# Supply.net
KiCad netlist of a schematic drawn in Altium Designer
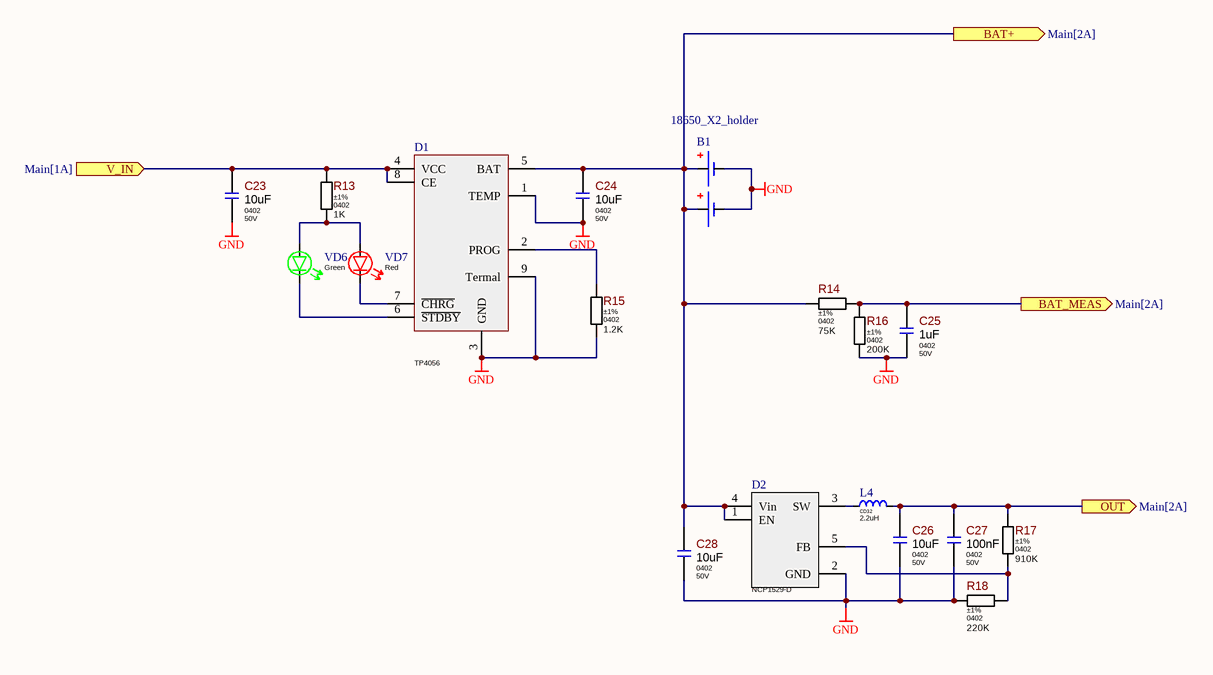
[diagram p0: Supply.SchDoc]

(export (version "E")
  (design (tool "Eeschema 10.0.6"))
  (components
    (comp (ref "B1")
      (value "18650_X2_holder")
      (footprint "18650_X2")
      (libsource (lib "Misc") (part "18650_X2_holder"))
    )
    (comp (ref "C23")
      (value "10uF")
      (footprint "Cap_0402")
      (description "10uF 50V  ±25% 0402 Ceramic Capacitor")
      (fields
        (field (name "TOLERANCE") "±25%")
        (field (name "PACKAGE") "0402")
        (field (name "VOLTAGE") "50V")
      )
      (libsource (lib "Capacitors") (part "Cap_0402_10uF"))
    )
    (comp (ref "C24")
      (value "10uF")
      (footprint "Cap_0402")
      (description "10uF 50V  ±25% 0402 Ceramic Capacitor")
      (fields
        (field (name "TOLERANCE") "±25%")
        (field (name "PACKAGE") "0402")
        (field (name "VOLTAGE") "50V")
      )
      (libsource (lib "Capacitors") (part "Cap_0402_10uF"))
    )
    (comp (ref "C25")
      (value "1uF")
      (footprint "Cap_0402")
      (description "1uF 50V  ±25% 0402 Ceramic Capacitor")
      (fields
        (field (name "TOLERANCE") "±25%")
        (field (name "PACKAGE") "0402")
        (field (name "VOLTAGE") "50V")
      )
      (libsource (lib "Capacitors") (part "Cap_0402_1uF"))
    )
    (comp (ref "C26")
      (value "10uF")
      (footprint "Cap_0402")
      (description "10uF 50V  ±25% 0402 Ceramic Capacitor")
      (fields
        (field (name "TOLERANCE") "±25%")
        (field (name "PACKAGE") "0402")
        (field (name "VOLTAGE") "50V")
      )
      (libsource (lib "Capacitors") (part "Cap_0402_10uF"))
    )
    (comp (ref "C27")
      (value "100nF")
      (footprint "Cap_0402")
      (description "100nF 50V  ±25% 0402 Ceramic Capacitor")
      (fields
        (field (name "TOLERANCE") "±25%")
        (field (name "PACKAGE") "0402")
        (field (name "VOLTAGE") "50V")
      )
      (libsource (lib "Capacitors") (part "Cap_0402_100nF"))
    )
    (comp (ref "C28")
      (value "10uF")
      (footprint "Cap_0402")
      (description "10uF 50V  ±25% 0402 Ceramic Capacitor")
      (fields
        (field (name "TOLERANCE") "±25%")
        (field (name "PACKAGE") "0402")
        (field (name "VOLTAGE") "50V")
      )
      (libsource (lib "Capacitors") (part "Cap_0402_10uF"))
    )
    (comp (ref "D1")
      (value "TP4056")
      (footprint "SOP-8-with thermal pad")
      (description "Lion Charger 1A")
      (fields (field (name "NAME") "TP4056"))
      (libsource (lib "IC") (part "TP4056"))
    )
    (comp (ref "D2")
      (value "NCP1529-D")
      (footprint "SOT-23-5")
      (description "In 2.7-5.5v 1A 1.7MHz DC-DC")
      (fields (field (name "NAME") "NCP1529-D"))
      (libsource (lib "IC") (part "NCP1529-D"))
    )
    (comp (ref "L4")
      (value "2.2uH")
      (footprint "Footprints:CD32")
      (fields (field (name "SIZE") "CD32") (field (name "Comment") "CD32"))
      (libsource (lib "Inductors") (part "CD32"))
    )
    (comp (ref "R13")
      (value "1K")
      (footprint "Res_0402")
      (description "±1% 1/16W 0402")
      (fields
        (field (name "VOLTAGE") "50V")
        (field (name "TOLERANCE") "±1%")
        (field (name "PACKAGE") "0402")
        (field (name "Comment") "Res_0402_1K")
      )
      (libsource (lib "Resistors") (part "Res_0402_1K"))
    )
    (comp (ref "R14")
      (value "75K")
      (footprint "Res_0402")
      (description "±1% 1/16W 0402")
      (fields
        (field (name "VOLTAGE") "50V")
        (field (name "TOLERANCE") "±1%")
        (field (name "PACKAGE") "0402")
        (field (name "Comment") "Res_0402_75K")
      )
      (libsource (lib "Resistors") (part "Res_0402_75K"))
    )
    (comp (ref "R15")
      (value "1.2K")
      (footprint "Res_0402")
      (description "±1% 1/16W 0402")
      (fields
        (field (name "VOLTAGE") "50V")
        (field (name "TOLERANCE") "±1%")
        (field (name "PACKAGE") "0402")
        (field (name "Comment") "Res_0402_1.2K")
      )
      (libsource (lib "Resistors") (part "Res_0402_1.2K"))
    )
    (comp (ref "R16")
      (value "200K")
      (footprint "Res_0402")
      (description "±1% 1/16W 0402")
      (fields
        (field (name "VOLTAGE") "50V")
        (field (name "TOLERANCE") "±1%")
        (field (name "PACKAGE") "0402")
        (field (name "Comment") "Res_0402_200K")
      )
      (libsource (lib "Resistors") (part "Res_0402_200K"))
    )
    (comp (ref "R17")
      (value "910K")
      (footprint "Res_0402")
      (description "±1% 1/16W 0402")
      (fields
        (field (name "VOLTAGE") "50V")
        (field (name "TOLERANCE") "±1%")
        (field (name "PACKAGE") "0402")
        (field (name "Comment") "Res_0402_910K")
      )
      (libsource (lib "Resistors") (part "Res_0402_910K"))
    )
    (comp (ref "R18")
      (value "220K")
      (footprint "Res_0402")
      (description "±1% 1/16W 0402")
      (fields
        (field (name "VOLTAGE") "50V")
        (field (name "TOLERANCE") "±1%")
        (field (name "PACKAGE") "0402")
        (field (name "Comment") "Res_0402_220K")
      )
      (libsource (lib "Resistors") (part "Res_0402_220K"))
    )
    (comp (ref "VD6")
      (value "0805_LED_GREEN")
      (footprint "Footprints:0805_LED_GREEN")
      (description "V=3v - 3.2v\r\nI=20mA")
      (fields (field (name "COLOR") "Green"))
      (libsource (lib "Diode") (part "0805_LED_GREEN"))
    )
    (comp (ref "VD7")
      (value "0805_LED_RED")
      (footprint "Footprints:0805_LED_RED")
      (description "V=2v - 2.2v\r\nI=20mA")
      (fields (field (name "COLOR") "Red"))
      (libsource (lib "Diode") (part "0805_LED_RED"))
    )
  )
  (nets
    (net (code "1") (name "/BAT+") (class "Default")
      (node (ref "B1") (pin "1") (pinfunction "+_1") (pintype "passive"))
      (node (ref "B1") (pin "3") (pinfunction "+_3") (pintype "passive"))
      (node (ref "C24") (pin "1") (pinfunction "1_1") (pintype "passive"))
      (node (ref "C28") (pin "1") (pinfunction "1_1") (pintype "passive"))
      (node (ref "D1") (pin "5") (pinfunction "BAT_5") (pintype "passive"))
      (node (ref "D2") (pin "1") (pinfunction "EN_1") (pintype "passive"))
      (node (ref "D2") (pin "4") (pinfunction "Vin_4") (pintype "passive"))
      (node (ref "R14") (pin "1") (pintype "passive"))
    )
    (net (code "2") (name "/BAT_MEAS") (class "Default")
      (node (ref "C25") (pin "2") (pinfunction "2_2") (pintype "passive"))
      (node (ref "R14") (pin "2") (pintype "passive"))
      (node (ref "R16") (pin "1") (pintype "passive"))
    )
    (net (code "3") (name "/OUT") (class "Default")
      (node (ref "C26") (pin "1") (pinfunction "1_1") (pintype "passive"))
      (node (ref "C27") (pin "1") (pinfunction "1_1") (pintype "passive"))
      (node (ref "L4") (pin "2") (pinfunction "2_2") (pintype "passive"))
      (node (ref "R17") (pin "1") (pintype "passive"))
    )
    (net (code "4") (name "/V_IN") (class "Default")
      (node (ref "C23") (pin "1") (pinfunction "1_1") (pintype "passive"))
      (node (ref "D1") (pin "4") (pinfunction "VCC_4") (pintype "passive"))
      (node (ref "D1") (pin "8") (pinfunction "CE_8") (pintype "passive"))
      (node (ref "R13") (pin "1") (pintype "passive"))
    )
    (net (code "5") (name "GND") (class "Default")
      (node (ref "B1") (pin "2") (pinfunction "-_2") (pintype "passive"))
      (node (ref "B1") (pin "4") (pinfunction "-_4") (pintype "passive"))
      (node (ref "C23") (pin "2") (pinfunction "2_2") (pintype "passive"))
      (node (ref "C24") (pin "2") (pinfunction "2_2") (pintype "passive"))
      (node (ref "C25") (pin "1") (pinfunction "1_1") (pintype "passive"))
      (node (ref "C26") (pin "2") (pinfunction "2_2") (pintype "passive"))
      (node (ref "C27") (pin "2") (pinfunction "2_2") (pintype "passive"))
      (node (ref "C28") (pin "2") (pinfunction "2_2") (pintype "passive"))
      (node (ref "D1") (pin "1") (pinfunction "TEMP_1") (pintype "passive"))
      (node (ref "D1") (pin "3") (pinfunction "GND_3") (pintype "passive"))
      (node (ref "D1") (pin "9") (pinfunction "Termal_9") (pintype "passive"))
      (node (ref "D2") (pin "2") (pinfunction "GND_2") (pintype "passive"))
      (node (ref "R15") (pin "2") (pintype "passive"))
      (node (ref "R16") (pin "2") (pintype "passive"))
      (node (ref "R18") (pin "2") (pintype "passive"))
    )
    (net (code "6") (name "Net-(D1-PROG)") (class "Default")
      (node (ref "D1") (pin "2") (pinfunction "PROG_2") (pintype "passive"))
      (node (ref "R15") (pin "1") (pintype "passive"))
    )
    (net (code "7") (name "Net-(D1-~{CHRG})") (class "Default")
      (node (ref "D1") (pin "7") (pinfunction "~{CHRG}_7") (pintype "passive"))
      (node (ref "VD7") (pin "2") (pinfunction "C_2") (pintype "passive"))
    )
    (net (code "8") (name "Net-(D1-~{STDBY})") (class "Default")
      (node (ref "D1") (pin "6") (pinfunction "~{STDBY}_6") (pintype "passive"))
      (node (ref "VD6") (pin "2") (pinfunction "C_2") (pintype "passive"))
    )
    (net (code "9") (name "Net-(D2-FB)") (class "Default")
      (node (ref "D2") (pin "5") (pinfunction "FB_5") (pintype "passive"))
      (node (ref "R17") (pin "2") (pintype "passive"))
      (node (ref "R18") (pin "1") (pintype "passive"))
    )
    (net (code "10") (name "Net-(D2-SW)") (class "Default")
      (node (ref "D2") (pin "3") (pinfunction "SW_3") (pintype "passive"))
      (node (ref "L4") (pin "1") (pinfunction "1_1") (pintype "passive"))
    )
    (net (code "11") (name "Net-(VD6-A)") (class "Default")
      (node (ref "R13") (pin "2") (pintype "passive"))
      (node (ref "VD6") (pin "1") (pinfunction "A_1") (pintype "passive"))
      (node (ref "VD7") (pin "1") (pinfunction "A_1") (pintype "passive"))
    )
  )
)
